# fpga.net
KiCad netlist of a schematic drawn in Altium Designer
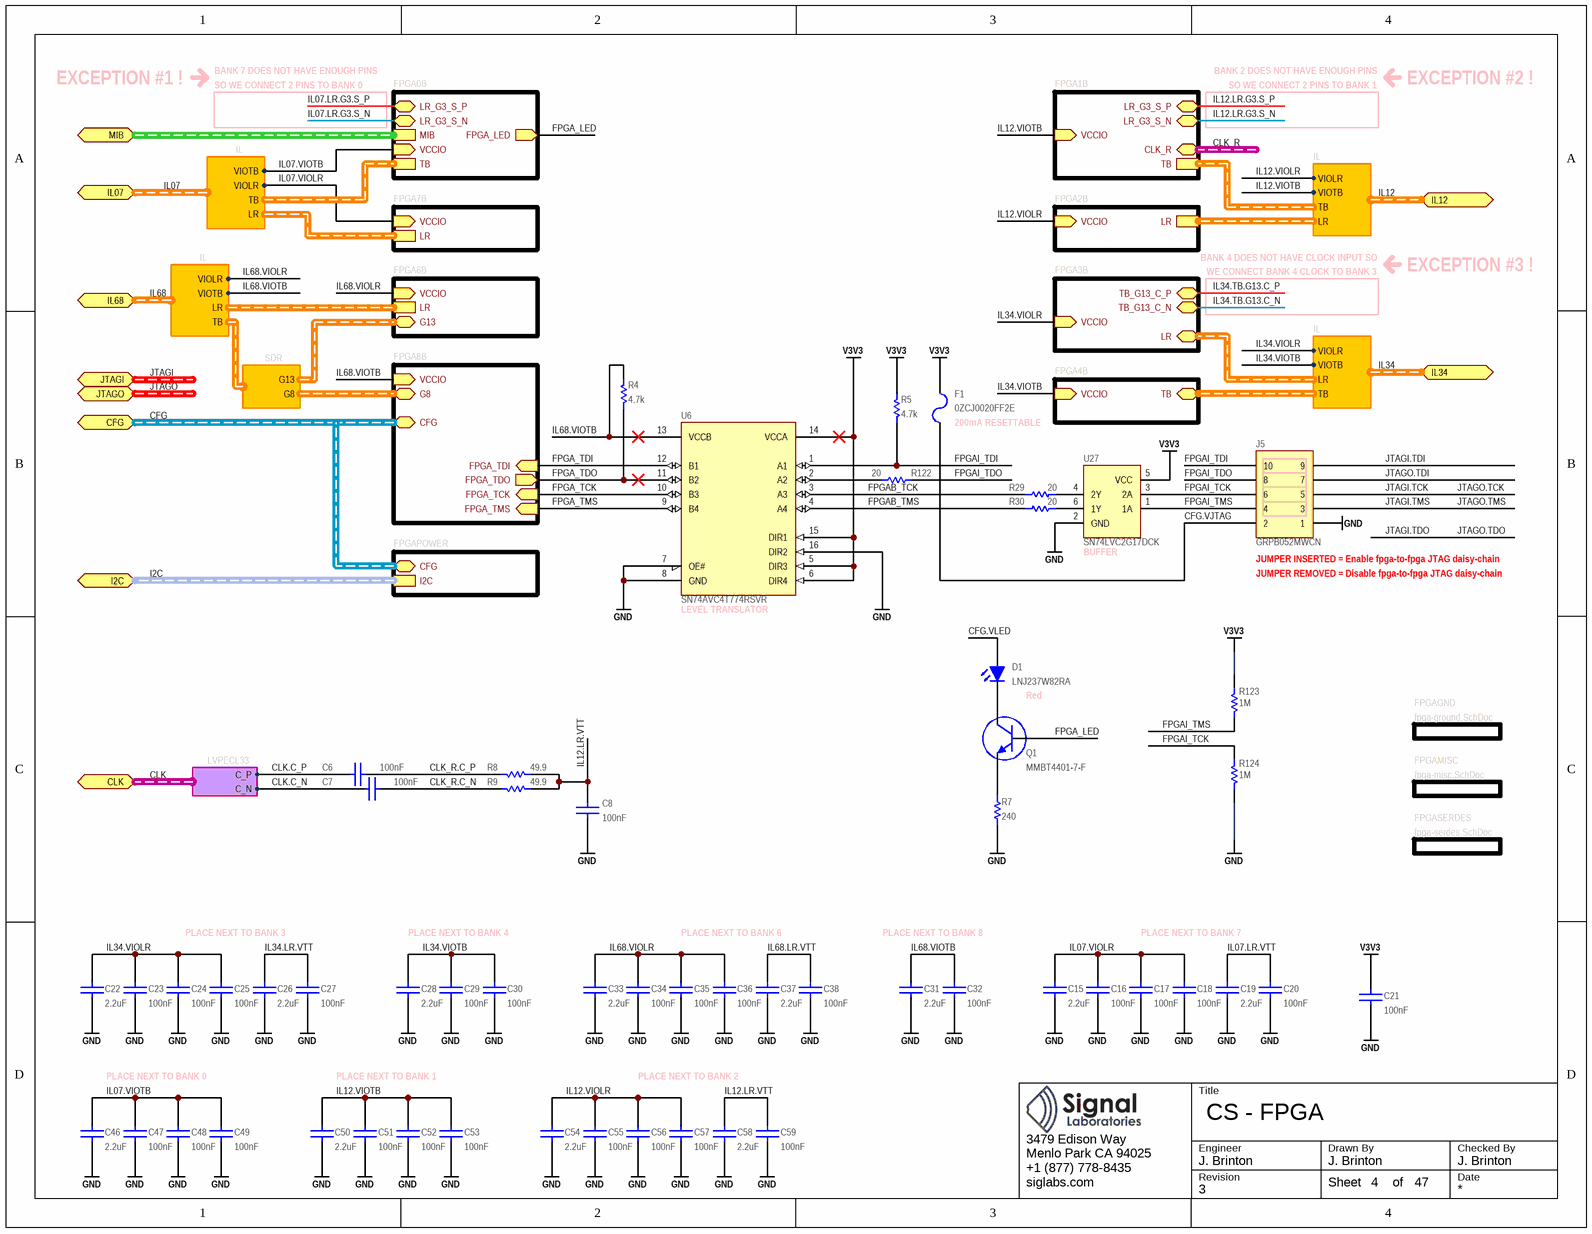
[diagram p0: fpga.SchDoc]

(export (version "E")
  (design (tool "Eeschema 10.0.6"))
  (components
    (comp (ref "C6")
      (value "100nF")
      (footprint "CAPC100X50X55L25N")
      (description "Ceramic Capacitor 100nF ±10% 50V X7R 0402")
      (fields (field (name "MANUFACTURER") "Murata") (field (name "TOLERANCE") "±10%"))
      (libsource (lib "generic") (part "CAP"))
    )
    (comp (ref "C7")
      (value "100nF")
      (footprint "CAPC100X50X55L25N")
      (description "Ceramic Capacitor 100nF ±10% 50V X7R 0402")
      (fields (field (name "MANUFACTURER") "Murata") (field (name "TOLERANCE") "±10%"))
      (libsource (lib "generic") (part "CAP"))
    )
    (comp (ref "C8")
      (value "100nF")
      (footprint "CAPC100X50X55L25N")
      (description "Ceramic Capacitor 100nF ±10% 50V X7R 0402")
      (fields (field (name "MANUFACTURER") "Murata") (field (name "TOLERANCE") "±10%"))
      (libsource (lib "generic") (part "CAP"))
    )
    (comp (ref "C15")
      (value "2.2uF")
      (footprint "CAPC160X80X90L20N")
      (description "Ceramic Capacitor 2.2uF ±20% 10V X7R 0603")
      (fields (field (name "MANUFACTURER") "TDK") (field (name "TOLERANCE") "±20%"))
      (libsource (lib "generic") (part "CAP"))
    )
    (comp (ref "C16")
      (value "100nF")
      (footprint "CAPC100X50X55L25N")
      (description "Ceramic Capacitor 100nF ±10% 50V X7R 0402")
      (fields (field (name "MANUFACTURER") "Murata") (field (name "TOLERANCE") "±10%"))
      (libsource (lib "generic") (part "CAP"))
    )
    (comp (ref "C17")
      (value "100nF")
      (footprint "CAPC100X50X55L25N")
      (description "Ceramic Capacitor 100nF ±10% 50V X7R 0402")
      (fields (field (name "MANUFACTURER") "Murata") (field (name "TOLERANCE") "±10%"))
      (libsource (lib "generic") (part "CAP"))
    )
    (comp (ref "C18")
      (value "100nF")
      (footprint "CAPC100X50X55L25N")
      (description "Ceramic Capacitor 100nF ±10% 50V X7R 0402")
      (fields (field (name "MANUFACTURER") "Murata") (field (name "TOLERANCE") "±10%"))
      (libsource (lib "generic") (part "CAP"))
    )
    (comp (ref "C19")
      (value "2.2uF")
      (footprint "CAPC160X80X90L20N")
      (description "Ceramic Capacitor 2.2uF ±20% 10V X7R 0603")
      (fields (field (name "MANUFACTURER") "TDK") (field (name "TOLERANCE") "±20%"))
      (libsource (lib "generic") (part "CAP"))
    )
    (comp (ref "C20")
      (value "100nF")
      (footprint "CAPC100X50X55L25N")
      (description "Ceramic Capacitor 100nF ±10% 50V X7R 0402")
      (fields (field (name "MANUFACTURER") "Murata") (field (name "TOLERANCE") "±10%"))
      (libsource (lib "generic") (part "CAP"))
    )
    (comp (ref "C21")
      (value "100nF")
      (footprint "CAPC100X50X55L25N")
      (description "Ceramic Capacitor 100nF ±10% 50V X7R 0402")
      (fields (field (name "MANUFACTURER") "Murata") (field (name "TOLERANCE") "±10%"))
      (libsource (lib "generic") (part "CAP"))
    )
    (comp (ref "C22")
      (value "2.2uF")
      (footprint "CAPC160X80X90L20N")
      (description "Ceramic Capacitor 2.2uF ±20% 10V X7R 0603")
      (fields (field (name "MANUFACTURER") "TDK") (field (name "TOLERANCE") "±20%"))
      (libsource (lib "generic") (part "CAP"))
    )
    (comp (ref "C23")
      (value "100nF")
      (footprint "CAPC100X50X55L25N")
      (description "Ceramic Capacitor 100nF ±10% 50V X7R 0402")
      (fields (field (name "MANUFACTURER") "Murata") (field (name "TOLERANCE") "±10%"))
      (libsource (lib "generic") (part "CAP"))
    )
    (comp (ref "C24")
      (value "100nF")
      (footprint "CAPC100X50X55L25N")
      (description "Ceramic Capacitor 100nF ±10% 50V X7R 0402")
      (fields (field (name "MANUFACTURER") "Murata") (field (name "TOLERANCE") "±10%"))
      (libsource (lib "generic") (part "CAP"))
    )
    (comp (ref "C25")
      (value "100nF")
      (footprint "CAPC100X50X55L25N")
      (description "Ceramic Capacitor 100nF ±10% 50V X7R 0402")
      (fields (field (name "MANUFACTURER") "Murata") (field (name "TOLERANCE") "±10%"))
      (libsource (lib "generic") (part "CAP"))
    )
    (comp (ref "C26")
      (value "2.2uF")
      (footprint "CAPC160X80X90L20N")
      (description "Ceramic Capacitor 2.2uF ±20% 10V X7R 0603")
      (fields (field (name "MANUFACTURER") "TDK") (field (name "TOLERANCE") "±20%"))
      (libsource (lib "generic") (part "CAP"))
    )
    (comp (ref "C27")
      (value "100nF")
      (footprint "CAPC100X50X55L25N")
      (description "Ceramic Capacitor 100nF ±10% 50V X7R 0402")
      (fields (field (name "MANUFACTURER") "Murata") (field (name "TOLERANCE") "±10%"))
      (libsource (lib "generic") (part "CAP"))
    )
    (comp (ref "C28")
      (value "2.2uF")
      (footprint "CAPC160X80X90L20N")
      (description "Ceramic Capacitor 2.2uF ±20% 10V X7R 0603")
      (fields (field (name "MANUFACTURER") "TDK") (field (name "TOLERANCE") "±20%"))
      (libsource (lib "generic") (part "CAP"))
    )
    (comp (ref "C29")
      (value "100nF")
      (footprint "CAPC100X50X55L25N")
      (description "Ceramic Capacitor 100nF ±10% 50V X7R 0402")
      (fields (field (name "MANUFACTURER") "Murata") (field (name "TOLERANCE") "±10%"))
      (libsource (lib "generic") (part "CAP"))
    )
    (comp (ref "C30")
      (value "100nF")
      (footprint "CAPC100X50X55L25N")
      (description "Ceramic Capacitor 100nF ±10% 50V X7R 0402")
      (fields (field (name "MANUFACTURER") "Murata") (field (name "TOLERANCE") "±10%"))
      (libsource (lib "generic") (part "CAP"))
    )
    (comp (ref "C31")
      (value "2.2uF")
      (footprint "CAPC160X80X90L20N")
      (description "Ceramic Capacitor 2.2uF ±20% 10V X7R 0603")
      (fields (field (name "MANUFACTURER") "TDK") (field (name "TOLERANCE") "±20%"))
      (libsource (lib "generic") (part "CAP"))
    )
    (comp (ref "C32")
      (value "100nF")
      (footprint "CAPC100X50X55L25N")
      (description "Ceramic Capacitor 100nF ±10% 50V X7R 0402")
      (fields (field (name "MANUFACTURER") "Murata") (field (name "TOLERANCE") "±10%"))
      (libsource (lib "generic") (part "CAP"))
    )
    (comp (ref "C33")
      (value "2.2uF")
      (footprint "CAPC160X80X90L20N")
      (description "Ceramic Capacitor 2.2uF ±20% 10V X7R 0603")
      (fields (field (name "MANUFACTURER") "TDK") (field (name "TOLERANCE") "±20%"))
      (libsource (lib "generic") (part "CAP"))
    )
    (comp (ref "C34")
      (value "100nF")
      (footprint "CAPC100X50X55L25N")
      (description "Ceramic Capacitor 100nF ±10% 50V X7R 0402")
      (fields (field (name "MANUFACTURER") "Murata") (field (name "TOLERANCE") "±10%"))
      (libsource (lib "generic") (part "CAP"))
    )
    (comp (ref "C35")
      (value "100nF")
      (footprint "CAPC100X50X55L25N")
      (description "Ceramic Capacitor 100nF ±10% 50V X7R 0402")
      (fields (field (name "MANUFACTURER") "Murata") (field (name "TOLERANCE") "±10%"))
      (libsource (lib "generic") (part "CAP"))
    )
    (comp (ref "C36")
      (value "100nF")
      (footprint "CAPC100X50X55L25N")
      (description "Ceramic Capacitor 100nF ±10% 50V X7R 0402")
      (fields (field (name "MANUFACTURER") "Murata") (field (name "TOLERANCE") "±10%"))
      (libsource (lib "generic") (part "CAP"))
    )
    (comp (ref "C37")
      (value "2.2uF")
      (footprint "CAPC160X80X90L20N")
      (description "Ceramic Capacitor 2.2uF ±20% 10V X7R 0603")
      (fields (field (name "MANUFACTURER") "TDK") (field (name "TOLERANCE") "±20%"))
      (libsource (lib "generic") (part "CAP"))
    )
    (comp (ref "C38")
      (value "100nF")
      (footprint "CAPC100X50X55L25N")
      (description "Ceramic Capacitor 100nF ±10% 50V X7R 0402")
      (fields (field (name "MANUFACTURER") "Murata") (field (name "TOLERANCE") "±10%"))
      (libsource (lib "generic") (part "CAP"))
    )
    (comp (ref "C46")
      (value "2.2uF")
      (footprint "CAPC160X80X90L20N")
      (description "Ceramic Capacitor 2.2uF ±20% 10V X7R 0603")
      (fields (field (name "MANUFACTURER") "TDK") (field (name "TOLERANCE") "±20%"))
      (libsource (lib "generic") (part "CAP"))
    )
    (comp (ref "C47")
      (value "100nF")
      (footprint "CAPC100X50X55L25N")
      (description "Ceramic Capacitor 100nF ±10% 50V X7R 0402")
      (fields (field (name "MANUFACTURER") "Murata") (field (name "TOLERANCE") "±10%"))
      (libsource (lib "generic") (part "CAP"))
    )
    (comp (ref "C48")
      (value "100nF")
      (footprint "CAPC100X50X55L25N")
      (description "Ceramic Capacitor 100nF ±10% 50V X7R 0402")
      (fields (field (name "MANUFACTURER") "Murata") (field (name "TOLERANCE") "±10%"))
      (libsource (lib "generic") (part "CAP"))
    )
    (comp (ref "C49")
      (value "100nF")
      (footprint "CAPC100X50X55L25N")
      (description "Ceramic Capacitor 100nF ±10% 50V X7R 0402")
      (fields (field (name "MANUFACTURER") "Murata") (field (name "TOLERANCE") "±10%"))
      (libsource (lib "generic") (part "CAP"))
    )
    (comp (ref "C50")
      (value "2.2uF")
      (footprint "CAPC160X80X90L20N")
      (description "Ceramic Capacitor 2.2uF ±20% 10V X7R 0603")
      (fields (field (name "MANUFACTURER") "TDK") (field (name "TOLERANCE") "±20%"))
      (libsource (lib "generic") (part "CAP"))
    )
    (comp (ref "C51")
      (value "100nF")
      (footprint "CAPC100X50X55L25N")
      (description "Ceramic Capacitor 100nF ±10% 50V X7R 0402")
      (fields (field (name "MANUFACTURER") "Murata") (field (name "TOLERANCE") "±10%"))
      (libsource (lib "generic") (part "CAP"))
    )
    (comp (ref "C52")
      (value "100nF")
      (footprint "CAPC100X50X55L25N")
      (description "Ceramic Capacitor 100nF ±10% 50V X7R 0402")
      (fields (field (name "MANUFACTURER") "Murata") (field (name "TOLERANCE") "±10%"))
      (libsource (lib "generic") (part "CAP"))
    )
    (comp (ref "C53")
      (value "100nF")
      (footprint "CAPC100X50X55L25N")
      (description "Ceramic Capacitor 100nF ±10% 50V X7R 0402")
      (fields (field (name "MANUFACTURER") "Murata") (field (name "TOLERANCE") "±10%"))
      (libsource (lib "generic") (part "CAP"))
    )
    (comp (ref "C54")
      (value "2.2uF")
      (footprint "CAPC160X80X90L20N")
      (description "Ceramic Capacitor 2.2uF ±20% 10V X7R 0603")
      (fields (field (name "MANUFACTURER") "TDK") (field (name "TOLERANCE") "±20%"))
      (libsource (lib "generic") (part "CAP"))
    )
    (comp (ref "C55")
      (value "100nF")
      (footprint "CAPC100X50X55L25N")
      (description "Ceramic Capacitor 100nF ±10% 50V X7R 0402")
      (fields (field (name "MANUFACTURER") "Murata") (field (name "TOLERANCE") "±10%"))
      (libsource (lib "generic") (part "CAP"))
    )
    (comp (ref "C56")
      (value "100nF")
      (footprint "CAPC100X50X55L25N")
      (description "Ceramic Capacitor 100nF ±10% 50V X7R 0402")
      (fields (field (name "MANUFACTURER") "Murata") (field (name "TOLERANCE") "±10%"))
      (libsource (lib "generic") (part "CAP"))
    )
    (comp (ref "C57")
      (value "100nF")
      (footprint "CAPC100X50X55L25N")
      (description "Ceramic Capacitor 100nF ±10% 50V X7R 0402")
      (fields (field (name "MANUFACTURER") "Murata") (field (name "TOLERANCE") "±10%"))
      (libsource (lib "generic") (part "CAP"))
    )
    (comp (ref "C58")
      (value "2.2uF")
      (footprint "CAPC160X80X90L20N")
      (description "Ceramic Capacitor 2.2uF ±20% 10V X7R 0603")
      (fields (field (name "MANUFACTURER") "TDK") (field (name "TOLERANCE") "±20%"))
      (libsource (lib "generic") (part "CAP"))
    )
    (comp (ref "C59")
      (value "100nF")
      (footprint "CAPC100X50X55L25N")
      (description "Ceramic Capacitor 100nF ±10% 50V X7R 0402")
      (fields (field (name "MANUFACTURER") "Murata") (field (name "TOLERANCE") "±10%"))
      (libsource (lib "generic") (part "CAP"))
    )
    (comp (ref "D1")
      (value "LNJ237W82RA")
      (footprint "0603_LED")
      (description "LED, SMT 0603, Color Red, 5mA, 1.85V")
      (fields (field (name "MANUFACTURER") "Panasonic"))
      (libsource (lib "generic") (part "LED0603RD"))
    )
    (comp (ref "F1")
      (value "0ZCJ0020FF2E")
      (footprint "generic:1206")
      (description "PTC Resettable Fuse, 0.2A, 30V, SMD 1206")
      (fields (field (name "MANUFACTURER") "Bell Fuse"))
      (libsource (lib "bel-fuse") (part "0ZCJ0020FF2E"))
    )
    (comp (ref "J5")
      (value "GRPB052MWCN")
      (footprint "sullins:GRPB052MWCN")
      (description "Male Header, 0.050\" Pitch, 2x5 Position, Right Angle")
      (fields (field (name "MANUFACTURER") "Sullins"))
      (libsource (lib "sullins") (part "GRPB052VWVN"))
    )
    (comp (ref "Q1")
      (value "MMBT4401-7-F")
      (footprint "generic:SOT23")
      (description "NPN Small Signal Transistor SMD SOT-23")
      (fields (field (name "MANUFACTURER P/N") "MMBT4401-7-F") (field (name "MANUFACTURER") "Diodes, Inc."))
      (libsource (lib "diodes_inc") (part "MMBT4401-7-F"))
    )
    (comp (ref "R4")
      (value "4.7k")
      (footprint "RESC1005X40N")
      (description "Thick Film Resistor 4.7k ±1% 0.1W 75V 0402")
      (fields (field (name "TOLERANCE") "±1%") (field (name "MANUFACTURER") "Panasonic"))
      (libsource (lib "generic") (part "RES"))
    )
    (comp (ref "R5")
      (value "4.7k")
      (footprint "RESC1005X40N")
      (description "Thick Film Resistor 4.7k ±1% 0.1W 75V 0402")
      (fields (field (name "TOLERANCE") "±1%") (field (name "MANUFACTURER") "Panasonic"))
      (libsource (lib "generic") (part "RES"))
    )
    (comp (ref "R7")
      (value "240")
      (footprint "RESC1005X40N")
      (description "Thick Film Resistor 240 ±1% 0.1W 75V 0402")
      (fields (field (name "TOLERANCE") "±1%") (field (name "MANUFACTURER") "Panasonic"))
      (libsource (lib "generic") (part "RES"))
    )
    (comp (ref "R8")
      (value "49.9")
      (footprint "RESC1005X40N")
      (description "Thick Film Resistor 49.9 ±1% 0.1W 50V 0402")
      (fields (field (name "TOLERANCE") "±1%") (field (name "MANUFACTURER") "Panasonic"))
      (libsource (lib "generic") (part "RES"))
    )
    (comp (ref "R9")
      (value "49.9")
      (footprint "RESC1005X40N")
      (description "Thick Film Resistor 49.9 ±1% 0.1W 50V 0402")
      (fields (field (name "TOLERANCE") "±1%") (field (name "MANUFACTURER") "Panasonic"))
      (libsource (lib "generic") (part "RES"))
    )
    (comp (ref "R29")
      (value "20")
      (footprint "RESC1005X40N")
      (description "Thick Film Resistor 20 ±1% 0.1W 75V 0402")
      (fields (field (name "TOLERANCE") "±1%") (field (name "MANUFACTURER") "Panasonic"))
      (libsource (lib "generic") (part "RES"))
    )
    (comp (ref "R30")
      (value "20")
      (footprint "RESC1005X40N")
      (description "Thick Film Resistor 20 ±1% 0.1W 75V 0402")
      (fields (field (name "TOLERANCE") "±1%") (field (name "MANUFACTURER") "Panasonic"))
      (libsource (lib "generic") (part "RES"))
    )
    (comp (ref "R122")
      (value "20")
      (footprint "RESC1005X40N")
      (description "Thick Film Resistor 20 ±1% 0.1W 75V 0402")
      (fields (field (name "TOLERANCE") "±1%") (field (name "MANUFACTURER") "Panasonic"))
      (libsource (lib "generic") (part "RES"))
    )
    (comp (ref "R123")
      (value "1M")
      (footprint "RESC1005X40N")
      (description "Thick Film Resistor 1M ±1% 0.1W 75V 0402")
      (fields (field (name "TOLERANCE") "±1%") (field (name "MANUFACTURER") "Panasonic"))
      (libsource (lib "generic") (part "RES"))
    )
    (comp (ref "R124")
      (value "1M")
      (footprint "RESC1005X40N")
      (description "Thick Film Resistor 1M ±1% 0.1W 75V 0402")
      (fields (field (name "TOLERANCE") "±1%") (field (name "MANUFACTURER") "Panasonic"))
      (libsource (lib "generic") (part "RES"))
    )
    (comp (ref "U6")
      (value "SN74AVC4T774RSVR")
      (footprint "RSV")
      (description "4-Bit Dual-Supply Bus Transceiver")
      (fields (field (name "MANUFACTURER") "Texas Instruments"))
      (libsource (lib "ti") (part "SN74AVC4T774RSVR"))
    )
    (comp (ref "U27")
      (value "SN74LVC2G17DCK")
      (footprint "texas_instruments:DCK-6")
      (description "Dual Schmitt-Trigger Buffer")
      (fields (field (name "MANUFACTURER") "Texas Instruments"))
      (libsource (lib "ti") (part "SN74LVC2G17DCK"))
    )
  )
  (nets
    (net (code "14") (name "/CFG.VJTAG") (class "Default")
      (node (ref "F1") (pin "2") (pinfunction "2_2") (pintype "passive"))
      (node (ref "J5") (pin "2") (pinfunction "2_2") (pintype "passive"))
    )
    (net (code "15") (name "/CFG.VLED") (class "Default")
      (node (ref "D1") (pin "1") (pinfunction "A_1") (pintype "passive"))
    )
    (net (code "16") (name "/CLK.C_N") (class "Default")
      (node (ref "C7") (pin "2") (pinfunction "2_2") (pintype "passive"))
    )
    (net (code "17") (name "/CLK.C_P") (class "Default")
      (node (ref "C6") (pin "2") (pinfunction "2_2") (pintype "passive"))
    )
    (net (code "18") (name "/CLK_R.C_N") (class "Default")
      (node (ref "C7") (pin "1") (pinfunction "1_1") (pintype "passive"))
      (node (ref "R9") (pin "2") (pinfunction "2_2") (pintype "passive"))
    )
    (net (code "19") (name "/CLK_R.C_P") (class "Default")
      (node (ref "C6") (pin "1") (pinfunction "1_1") (pintype "passive"))
      (node (ref "R8") (pin "2") (pinfunction "2_2") (pintype "passive"))
    )
    (net (code "21") (name "/FPGAB_TCK") (class "Default")
      (node (ref "R29") (pin "1") (pinfunction "1_1") (pintype "passive"))
      (node (ref "U6") (pin "3") (pinfunction "A3_3") (pintype "bidirectional"))
    )
    (net (code "22") (name "/FPGAB_TMS") (class "Default")
      (node (ref "R30") (pin "1") (pinfunction "1_1") (pintype "passive"))
      (node (ref "U6") (pin "4") (pinfunction "A4_4") (pintype "bidirectional"))
    )
    (net (code "23") (name "/FPGAI_TCK") (class "Default")
      (node (ref "J5") (pin "6") (pinfunction "6_6") (pintype "passive"))
      (node (ref "R124") (pin "1") (pinfunction "1_1") (pintype "passive"))
      (node (ref "U27") (pin "3") (pinfunction "2A_3") (pintype "passive"))
    )
    (net (code "24") (name "/FPGAI_TDI") (class "Default")
      (node (ref "J5") (pin "10") (pinfunction "10_10") (pintype "passive"))
      (node (ref "R5") (pin "1") (pinfunction "1_1") (pintype "passive"))
      (node (ref "U6") (pin "1") (pinfunction "A1_1") (pintype "bidirectional"))
    )
    (net (code "25") (name "/FPGAI_TDO") (class "Default")
      (node (ref "J5") (pin "8") (pinfunction "8_8") (pintype "passive"))
      (node (ref "R122") (pin "2") (pinfunction "2_2") (pintype "passive"))
    )
    (net (code "26") (name "/FPGAI_TMS") (class "Default")
      (node (ref "J5") (pin "4") (pinfunction "4_4") (pintype "passive"))
      (node (ref "R123") (pin "2") (pinfunction "2_2") (pintype "passive"))
      (node (ref "U27") (pin "1") (pinfunction "1A_1") (pintype "passive"))
    )
    (net (code "27") (name "/FPGA_LED") (class "Default")
      (node (ref "Q1") (pin "1") (pinfunction "B_1") (pintype "passive"))
    )
    (net (code "28") (name "/FPGA_TCK") (class "Default")
      (node (ref "U6") (pin "10") (pinfunction "B3_10") (pintype "bidirectional"))
    )
    (net (code "29") (name "/FPGA_TDI") (class "Default")
      (node (ref "U6") (pin "12") (pinfunction "B1_12") (pintype "bidirectional"))
    )
    (net (code "30") (name "/FPGA_TDO") (class "Default")
      (node (ref "R4") (pin "1") (pinfunction "1_1") (pintype "passive"))
      (node (ref "U6") (pin "11") (pinfunction "B2_11") (pintype "bidirectional"))
    )
    (net (code "31") (name "/FPGA_TMS") (class "Default")
      (node (ref "U6") (pin "9") (pinfunction "B4_9") (pintype "bidirectional"))
    )
    (net (code "34") (name "/IL07.LR.VTT") (class "Default")
      (node (ref "C19") (pin "2") (pinfunction "2_2") (pintype "passive"))
      (node (ref "C20") (pin "2") (pinfunction "2_2") (pintype "passive"))
    )
    (net (code "35") (name "/IL07.VIOLR") (class "Default")
      (node (ref "C15") (pin "2") (pinfunction "2_2") (pintype "passive"))
      (node (ref "C16") (pin "2") (pinfunction "2_2") (pintype "passive"))
      (node (ref "C17") (pin "2") (pinfunction "2_2") (pintype "passive"))
      (node (ref "C18") (pin "2") (pinfunction "2_2") (pintype "passive"))
    )
    (net (code "36") (name "/IL07.VIOTB") (class "Default")
      (node (ref "C46") (pin "2") (pinfunction "2_2") (pintype "passive"))
      (node (ref "C47") (pin "2") (pinfunction "2_2") (pintype "passive"))
      (node (ref "C48") (pin "2") (pinfunction "2_2") (pintype "passive"))
      (node (ref "C49") (pin "2") (pinfunction "2_2") (pintype "passive"))
    )
    (net (code "39") (name "/IL12.LR.VTT") (class "Default")
      (node (ref "C58") (pin "2") (pinfunction "2_2") (pintype "passive"))
      (node (ref "C59") (pin "2") (pinfunction "2_2") (pintype "passive"))
      (node (ref "C8") (pin "2") (pinfunction "2_2") (pintype "passive"))
      (node (ref "R8") (pin "1") (pinfunction "1_1") (pintype "passive"))
      (node (ref "R9") (pin "1") (pinfunction "1_1") (pintype "passive"))
    )
    (net (code "40") (name "/IL12.VIOLR") (class "Default")
      (node (ref "C54") (pin "2") (pinfunction "2_2") (pintype "passive"))
      (node (ref "C55") (pin "2") (pinfunction "2_2") (pintype "passive"))
      (node (ref "C56") (pin "2") (pinfunction "2_2") (pintype "passive"))
      (node (ref "C57") (pin "2") (pinfunction "2_2") (pintype "passive"))
    )
    (net (code "41") (name "/IL12.VIOTB") (class "Default")
      (node (ref "C50") (pin "2") (pinfunction "2_2") (pintype "passive"))
      (node (ref "C51") (pin "2") (pinfunction "2_2") (pintype "passive"))
      (node (ref "C52") (pin "2") (pinfunction "2_2") (pintype "passive"))
      (node (ref "C53") (pin "2") (pinfunction "2_2") (pintype "passive"))
    )
    (net (code "42") (name "/IL34.LR.VTT") (class "Default")
      (node (ref "C26") (pin "2") (pinfunction "2_2") (pintype "passive"))
      (node (ref "C27") (pin "2") (pinfunction "2_2") (pintype "passive"))
    )
    (net (code "45") (name "/IL34.VIOLR") (class "Default")
      (node (ref "C22") (pin "2") (pinfunction "2_2") (pintype "passive"))
      (node (ref "C23") (pin "2") (pinfunction "2_2") (pintype "passive"))
      (node (ref "C24") (pin "2") (pinfunction "2_2") (pintype "passive"))
      (node (ref "C25") (pin "2") (pinfunction "2_2") (pintype "passive"))
    )
    (net (code "46") (name "/IL34.VIOTB") (class "Default")
      (node (ref "C28") (pin "2") (pinfunction "2_2") (pintype "passive"))
      (node (ref "C29") (pin "2") (pinfunction "2_2") (pintype "passive"))
      (node (ref "C30") (pin "2") (pinfunction "2_2") (pintype "passive"))
    )
    (net (code "47") (name "/IL68.LR.VTT") (class "Default")
      (node (ref "C37") (pin "2") (pinfunction "2_2") (pintype "passive"))
      (node (ref "C38") (pin "2") (pinfunction "2_2") (pintype "passive"))
    )
    (net (code "48") (name "/IL68.VIOLR") (class "Default")
      (node (ref "C33") (pin "2") (pinfunction "2_2") (pintype "passive"))
      (node (ref "C34") (pin "2") (pinfunction "2_2") (pintype "passive"))
      (node (ref "C35") (pin "2") (pinfunction "2_2") (pintype "passive"))
      (node (ref "C36") (pin "2") (pinfunction "2_2") (pintype "passive"))
    )
    (net (code "49") (name "/IL68.VIOTB") (class "Default")
      (node (ref "C31") (pin "2") (pinfunction "2_2") (pintype "passive"))
      (node (ref "C32") (pin "2") (pinfunction "2_2") (pintype "passive"))
      (node (ref "R4") (pin "2") (pinfunction "2_2") (pintype "passive"))
      (node (ref "U6") (pin "13") (pinfunction "VCCB_13") (pintype "power_in"))
    )
    (net (code "50") (name "/JTAGI.TCK") (class "Default")
      (node (ref "J5") (pin "5") (pinfunction "5_5") (pintype "passive"))
    )
    (net (code "51") (name "/JTAGI.TDI") (class "Default")
      (node (ref "J5") (pin "9") (pinfunction "9_9") (pintype "passive"))
    )
    (net (code "53") (name "/JTAGI.TMS") (class "Default")
      (node (ref "J5") (pin "3") (pinfunction "3_3") (pintype "passive"))
    )
    (net (code "54") (name "/JTAGO.TDI") (class "Default")
      (node (ref "J5") (pin "7") (pinfunction "7_7") (pintype "passive"))
    )
    (net (code "69") (name "GND") (class "Default")
      (node (ref "C15") (pin "1") (pinfunction "1_1") (pintype "passive"))
      (node (ref "C16") (pin "1") (pinfunction "1_1") (pintype "passive"))
      (node (ref "C17") (pin "1") (pinfunction "1_1") (pintype "passive"))
      (node (ref "C18") (pin "1") (pinfunction "1_1") (pintype "passive"))
      (node (ref "C19") (pin "1") (pinfunction "1_1") (pintype "passive"))
      (node (ref "C20") (pin "1") (pinfunction "1_1") (pintype "passive"))
      (node (ref "C21") (pin "1") (pinfunction "1_1") (pintype "passive"))
      (node (ref "C22") (pin "1") (pinfunction "1_1") (pintype "passive"))
      (node (ref "C23") (pin "1") (pinfunction "1_1") (pintype "passive"))
      (node (ref "C24") (pin "1") (pinfunction "1_1") (pintype "passive"))
      (node (ref "C25") (pin "1") (pinfunction "1_1") (pintype "passive"))
      (node (ref "C26") (pin "1") (pinfunction "1_1") (pintype "passive"))
      (node (ref "C27") (pin "1") (pinfunction "1_1") (pintype "passive"))
      (node (ref "C28") (pin "1") (pinfunction "1_1") (pintype "passive"))
      (node (ref "C29") (pin "1") (pinfunction "1_1") (pintype "passive"))
      (node (ref "C30") (pin "1") (pinfunction "1_1") (pintype "passive"))
      (node (ref "C31") (pin "1") (pinfunction "1_1") (pintype "passive"))
      (node (ref "C32") (pin "1") (pinfunction "1_1") (pintype "passive"))
      (node (ref "C33") (pin "1") (pinfunction "1_1") (pintype "passive"))
      (node (ref "C34") (pin "1") (pinfunction "1_1") (pintype "passive"))
      (node (ref "C35") (pin "1") (pinfunction "1_1") (pintype "passive"))
      (node (ref "C36") (pin "1") (pinfunction "1_1") (pintype "passive"))
      (node (ref "C37") (pin "1") (pinfunction "1_1") (pintype "passive"))
      (node (ref "C38") (pin "1") (pinfunction "1_1") (pintype "passive"))
      (node (ref "C46") (pin "1") (pinfunction "1_1") (pintype "passive"))
      (node (ref "C47") (pin "1") (pinfunction "1_1") (pintype "passive"))
      (node (ref "C48") (pin "1") (pinfunction "1_1") (pintype "passive"))
      (node (ref "C49") (pin "1") (pinfunction "1_1") (pintype "passive"))
      (node (ref "C50") (pin "1") (pinfunction "1_1") (pintype "passive"))
      (node (ref "C51") (pin "1") (pinfunction "1_1") (pintype "passive"))
      (node (ref "C52") (pin "1") (pinfunction "1_1") (pintype "passive"))
      (node (ref "C53") (pin "1") (pinfunction "1_1") (pintype "passive"))
      (node (ref "C54") (pin "1") (pinfunction "1_1") (pintype "passive"))
      (node (ref "C55") (pin "1") (pinfunction "1_1") (pintype "passive"))
      (node (ref "C56") (pin "1") (pinfunction "1_1") (pintype "passive"))
      (node (ref "C57") (pin "1") (pinfunction "1_1") (pintype "passive"))
      (node (ref "C58") (pin "1") (pinfunction "1_1") (pintype "passive"))
      (node (ref "C59") (pin "1") (pinfunction "1_1") (pintype "passive"))
      (node (ref "C8") (pin "1") (pinfunction "1_1") (pintype "passive"))
      (node (ref "J5") (pin "1") (pinfunction "1_1") (pintype "passive"))
      (node (ref "R124") (pin "2") (pinfunction "2_2") (pintype "passive"))
      (node (ref "R7") (pin "2") (pinfunction "2_2") (pintype "passive"))
      (node (ref "U27") (pin "2") (pinfunction "GND_2") (pintype "passive"))
      (node (ref "U6") (pin "16") (pinfunction "DIR2_16") (pintype "input"))
      (node (ref "U6") (pin "7") (pinfunction "OE#_7") (pintype "passive"))
      (node (ref "U6") (pin "8") (pinfunction "GND_8") (pintype "power_in"))
    )
    (net (code "70") (name "Net-(D1-K)") (class "Default")
      (node (ref "D1") (pin "2") (pinfunction "K_2") (pintype "passive"))
      (node (ref "Q1") (pin "3") (pinfunction "C_3") (pintype "passive"))
    )
    (net (code "71") (name "Net-(Q1-E)") (class "Default")
      (node (ref "Q1") (pin "2") (pinfunction "E_2") (pintype "passive"))
      (node (ref "R7") (pin "1") (pinfunction "1_1") (pintype "passive"))
    )
    (net (code "72") (name "Net-(U6-A2)") (class "Default")
      (node (ref "R122") (pin "1") (pinfunction "1_1") (pintype "passive"))
      (node (ref "U6") (pin "2") (pinfunction "A2_2") (pintype "bidirectional"))
    )
    (net (code "73") (name "Net-(U27-1Y)") (class "Default")
      (node (ref "R30") (pin "2") (pinfunction "2_2") (pintype "passive"))
      (node (ref "U27") (pin "6") (pinfunction "1Y_6") (pintype "passive"))
    )
    (net (code "74") (name "Net-(U27-2Y)") (class "Default")
      (node (ref "R29") (pin "2") (pinfunction "2_2") (pintype "passive"))
      (node (ref "U27") (pin "4") (pinfunction "2Y_4") (pintype "passive"))
    )
    (net (code "75") (name "V3V3") (class "Default")
      (node (ref "C21") (pin "2") (pinfunction "2_2") (pintype "passive"))
      (node (ref "F1") (pin "1") (pinfunction "1_1") (pintype "passive"))
      (node (ref "R123") (pin "1") (pinfunction "1_1") (pintype "passive"))
      (node (ref "R5") (pin "2") (pinfunction "2_2") (pintype "passive"))
      (node (ref "U27") (pin "5") (pinfunction "VCC_5") (pintype "passive"))
      (node (ref "U6") (pin "14") (pinfunction "VCCA_14") (pintype "power_in"))
      (node (ref "U6") (pin "15") (pinfunction "DIR1_15") (pintype "input"))
      (node (ref "U6") (pin "5") (pinfunction "DIR3_5") (pintype "input"))
      (node (ref "U6") (pin "6") (pinfunction "DIR4_6") (pintype "input"))
    )
  )
)
